# ESP32_with_USBC.net
KiCad netlist of a schematic drawn in Altium Designer
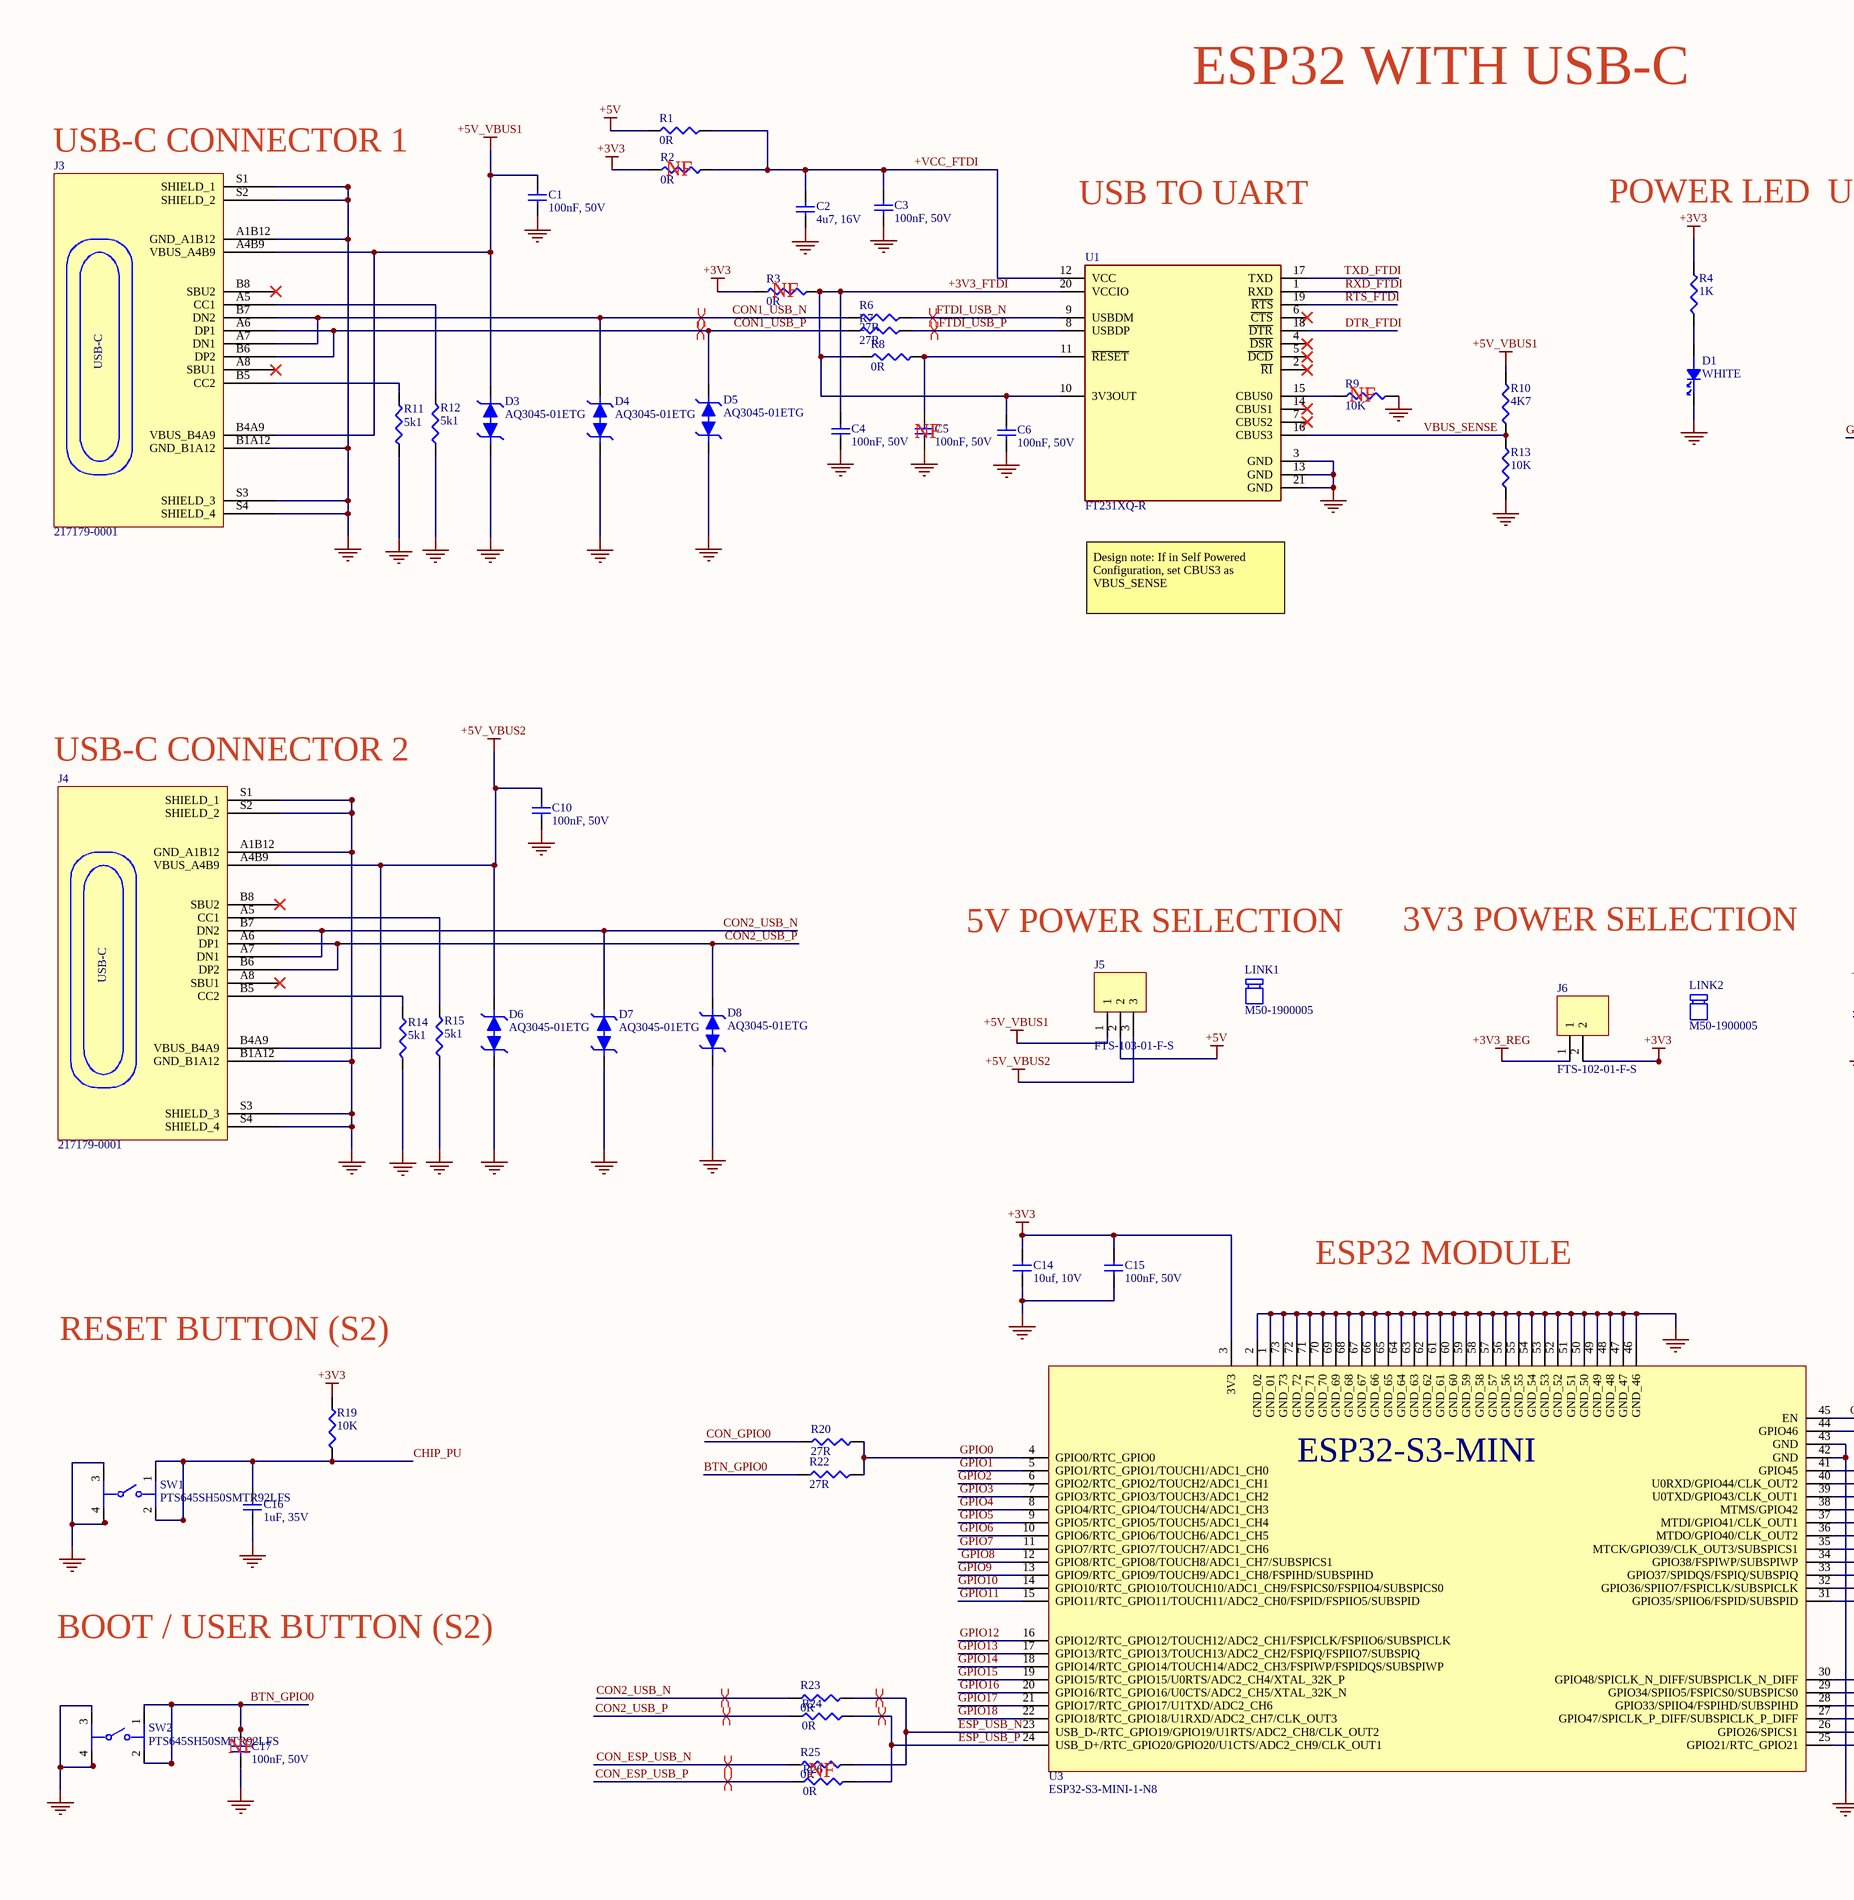
[diagram p0: ESP32 with USBC.SchDoc, left]
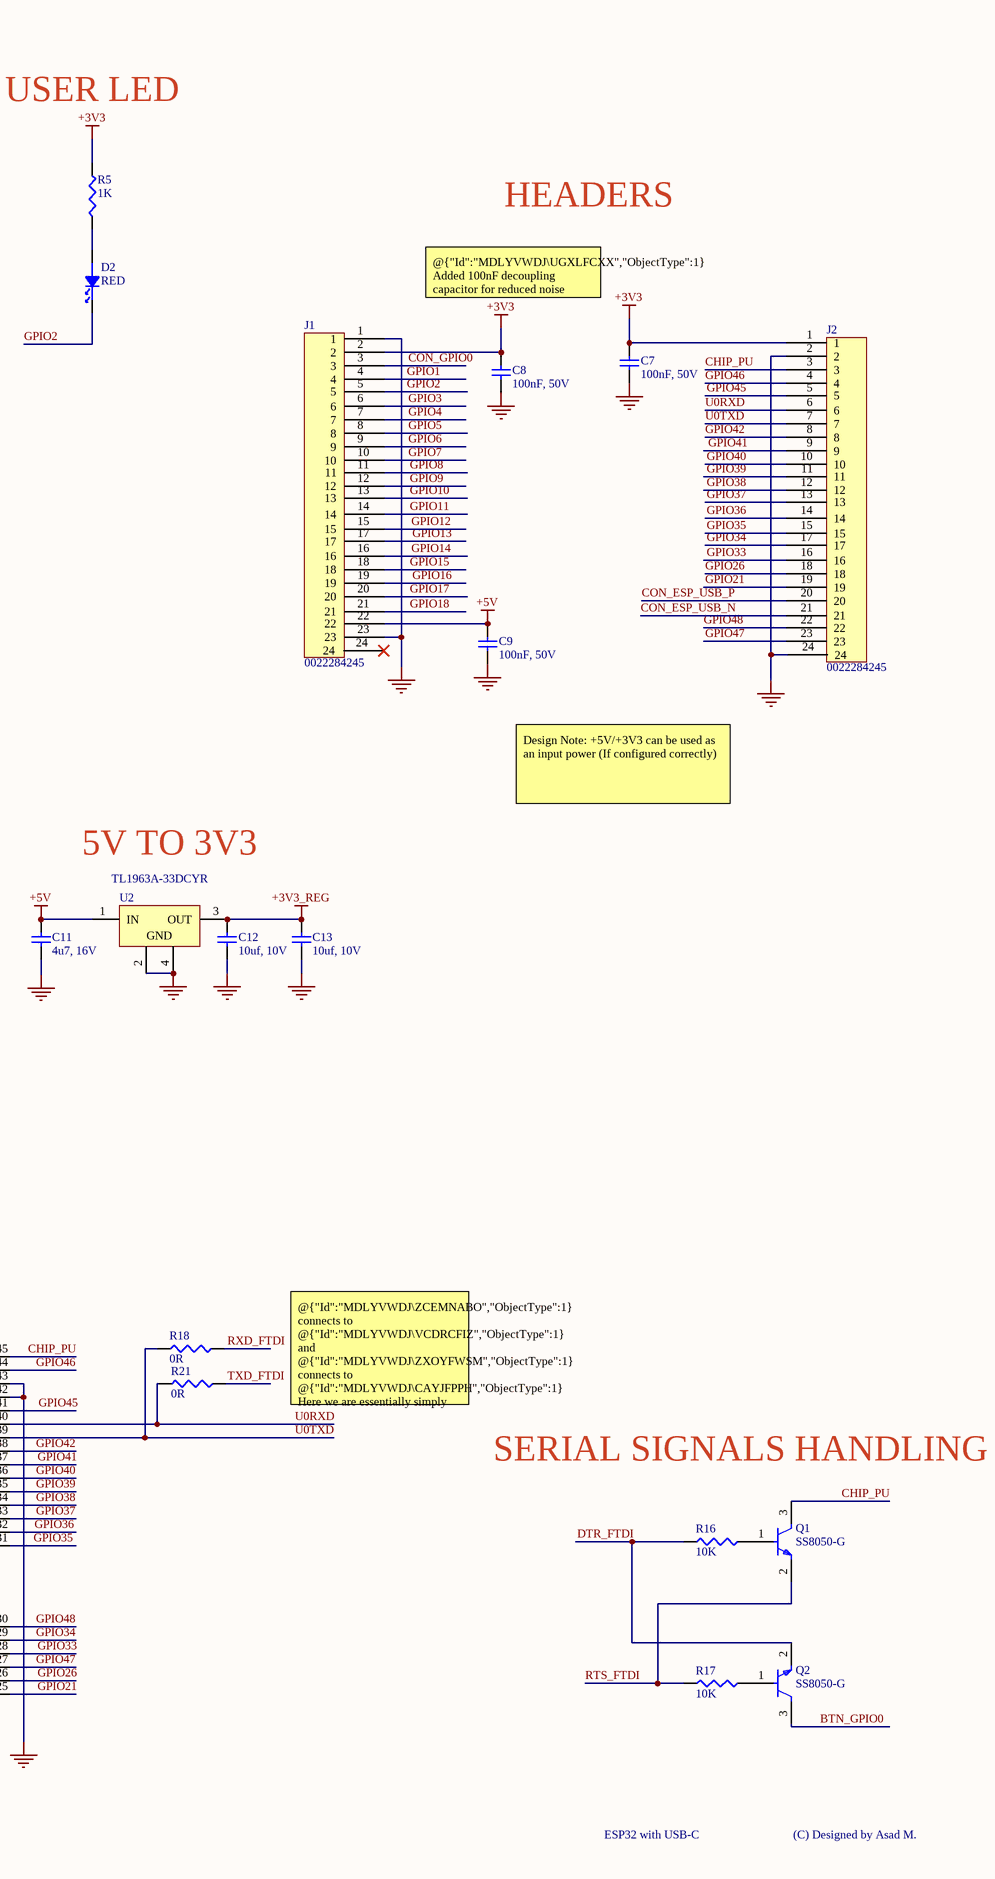
[diagram p1: ESP32 with USBC.SchDoc, right]

(export (version "E")
  (design (tool "Eeschema 10.0.6"))
  (components
    (comp (ref "C1")
      (value "100nF, 50V")
      (footprint "CAPC1005X55N")
      (description "CAP CER 0.1UF 50V X7R 0402")
      (fields
        (field (name "MANUFACTURER") "Samsung")
        (field (name "MANUFACTURER PART NUMBER") "CL05B104KB5NNNC")
      )
      (libsource (lib "Schlib") (part "CL05B104KB5NNNC"))
    )
    (comp (ref "C2")
      (value "4u7, 16V")
      (footprint "CAPC1005X55N")
      (description "CAP CER 4.7UF 16V X5R 0402")
      (fields
        (field (name "MANUFACTURER") "Samsung")
        (field (name "MANUFACTURER PART NUMBER") "CL05A475MO5NUNC")
      )
      (libsource (lib "Schlib") (part "CL05A475MO5NUNC"))
    )
    (comp (ref "C3")
      (value "100nF, 50V")
      (footprint "CAPC1005X55N")
      (description "CAP CER 0.1UF 50V X7R 0402")
      (fields
        (field (name "MANUFACTURER") "Samsung")
        (field (name "MANUFACTURER PART NUMBER") "CL05B104KB5NNNC")
      )
      (libsource (lib "Schlib") (part "CL05B104KB5NNNC"))
    )
    (comp (ref "C4")
      (value "100nF, 50V")
      (footprint "CAPC1005X55N")
      (description "CAP CER 0.1UF 50V X7R 0402")
      (fields
        (field (name "MANUFACTURER") "Samsung")
        (field (name "MANUFACTURER PART NUMBER") "CL05B104KB5NNNC")
      )
      (libsource (lib "Schlib") (part "CL05B104KB5NNNC"))
    )
    (comp (ref "C5")
      (value "100nF, 50V")
      (footprint "CAPC1005X55N")
      (description "CAP CER 0.1UF 50V X7R 0402")
      (fields
        (field (name "MANUFACTURER") "Samsung")
        (field (name "MANUFACTURER PART NUMBER") "CL05B104KB5NNNC")
      )
      (libsource (lib "Schlib") (part "CL05B104KB5NNNC"))
    )
    (comp (ref "C6")
      (value "100nF, 50V")
      (footprint "CAPC1005X55N")
      (description "CAP CER 0.1UF 50V X7R 0402")
      (fields
        (field (name "MANUFACTURER") "Samsung")
        (field (name "MANUFACTURER PART NUMBER") "CL05B104KB5NNNC")
      )
      (libsource (lib "Schlib") (part "CL05B104KB5NNNC"))
    )
    (comp (ref "C7")
      (value "100nF, 50V")
      (footprint "CAPC1005X55N")
      (description "CAP CER 0.1UF 50V X7R 0402")
      (fields
        (field (name "MANUFACTURER") "Samsung")
        (field (name "MANUFACTURER PART NUMBER") "CL05B104KB5NNNC")
      )
      (libsource (lib "Schlib") (part "CL05B104KB5NNNC"))
    )
    (comp (ref "C8")
      (value "100nF, 50V")
      (footprint "CAPC1005X55N")
      (description "CAP CER 0.1UF 50V X7R 0402")
      (fields
        (field (name "MANUFACTURER") "Samsung")
        (field (name "MANUFACTURER PART NUMBER") "CL05B104KB5NNNC")
      )
      (libsource (lib "Schlib") (part "CL05B104KB5NNNC"))
    )
    (comp (ref "C9")
      (value "100nF, 50V")
      (footprint "CAPC1005X55N")
      (description "CAP CER 0.1UF 50V X7R 0402")
      (fields
        (field (name "MANUFACTURER") "Samsung")
        (field (name "MANUFACTURER PART NUMBER") "CL05B104KB5NNNC")
      )
      (libsource (lib "Schlib") (part "CL05B104KB5NNNC"))
    )
    (comp (ref "C10")
      (value "100nF, 50V")
      (footprint "CAPC1005X55N")
      (description "CAP CER 0.1UF 50V X7R 0402")
      (fields
        (field (name "MANUFACTURER") "Samsung")
        (field (name "MANUFACTURER PART NUMBER") "CL05B104KB5NNNC")
      )
      (libsource (lib "Schlib") (part "CL05B104KB5NNNC"))
    )
    (comp (ref "C11")
      (value "4u7, 16V")
      (footprint "CAPC1005X55N")
      (description "CAP CER 4.7UF 16V X5R 0402")
      (fields
        (field (name "MANUFACTURER") "Samsung")
        (field (name "MANUFACTURER PART NUMBER") "CL05A475MO5NUNC")
      )
      (libsource (lib "Schlib") (part "CL05A475MO5NUNC"))
    )
    (comp (ref "C12")
      (value "10uf, 10V")
      (footprint "CAPC1005X55N")
      (description "CAP CER 10UF 10V X5R 0402")
      (fields
        (field (name "MANUFACTURER") "Samsung")
        (field (name "MANUFACTURER PART NUMBER") "CL05A106MP8NUB8")
      )
      (libsource (lib "Schlib") (part "CL05A106MP8NUB8"))
    )
    (comp (ref "C13")
      (value "10uf, 10V")
      (footprint "CAPC1005X55N")
      (description "CAP CER 10UF 10V X5R 0402")
      (fields
        (field (name "MANUFACTURER") "Samsung")
        (field (name "MANUFACTURER PART NUMBER") "CL05A106MP8NUB8")
      )
      (libsource (lib "Schlib") (part "CL05A106MP8NUB8"))
    )
    (comp (ref "C14")
      (value "10uf, 10V")
      (footprint "CAPC1005X55N")
      (description "CAP CER 10UF 10V X5R 0402")
      (fields
        (field (name "MANUFACTURER") "Samsung")
        (field (name "MANUFACTURER PART NUMBER") "CL05A106MP8NUB8")
      )
      (libsource (lib "Schlib") (part "CL05A106MP8NUB8"))
    )
    (comp (ref "C15")
      (value "100nF, 50V")
      (footprint "CAPC1005X55N")
      (description "CAP CER 0.1UF 50V X7R 0402")
      (fields
        (field (name "MANUFACTURER") "Samsung")
        (field (name "MANUFACTURER PART NUMBER") "CL05B104KB5NNNC")
      )
      (libsource (lib "Schlib") (part "CL05B104KB5NNNC"))
    )
    (comp (ref "C16")
      (value "1uF, 35V")
      (footprint "CAPC1005X55N")
      (description "CAP CER 1UF 35V X5R 0402")
      (fields
        (field (name "MANUFACTURER") "Samsung")
        (field (name "MANUFACTURER PART NUMBER") "CL05A105KL5NRNC")
      )
      (libsource (lib "Schlib") (part "CL05A105KL5NRNC"))
    )
    (comp (ref "C17")
      (value "100nF, 50V")
      (footprint "CAPC1005X55N")
      (description "CAP CER 0.1UF 50V X7R 0402")
      (fields
        (field (name "MANUFACTURER") "Samsung")
        (field (name "MANUFACTURER PART NUMBER") "CL05B104KB5NNNC")
      )
      (libsource (lib "Schlib") (part "CL05B104KB5NNNC"))
    )
    (comp (ref "D1")
      (value "WHITE")
      (description "LED COOL WHITE DIFFUSED 0402 SMD")
      (fields
        (field (name "MANUFACTURER") "Vishay")
        (field (name "MANUFACTURER PART NUMBER") "VLMW1500-GS08")
      )
      (libsource (lib "Schlib") (part "VLMW1500-GS08"))
    )
    (comp (ref "D2")
      (value "RED")
      (description "LED RED 0402 SMD")
      (fields
        (field (name "MANUFACTURER") "Vishay")
        (field (name "MANUFACTURER PART NUMBER") "VLMS1500-GS08")
      )
      (libsource (lib "Schlib") (part "VLMS1500-GS08"))
    )
    (comp (ref "D3")
      (value "AQ3045-01ETG")
      (description "TVS DIODE 5.3VWM 12VC SOD882")
      (fields (field (name "MANUFACTURER") "Littelfuse") (field (name "LCSC PART NUMBER") "C3710326"))
      (libsource (lib "Schlib") (part "AQ3045-01ETG"))
    )
    (comp (ref "D4")
      (value "AQ3045-01ETG")
      (description "TVS DIODE 5.3VWM 12VC SOD882")
      (fields (field (name "MANUFACTURER") "Littelfuse") (field (name "LCSC PART NUMBER") "C3710326"))
      (libsource (lib "Schlib") (part "AQ3045-01ETG"))
    )
    (comp (ref "D5")
      (value "AQ3045-01ETG")
      (description "TVS DIODE 5.3VWM 12VC SOD882")
      (fields (field (name "MANUFACTURER") "Littelfuse") (field (name "LCSC PART NUMBER") "C3710326"))
      (libsource (lib "Schlib") (part "AQ3045-01ETG"))
    )
    (comp (ref "D6")
      (value "AQ3045-01ETG")
      (description "TVS DIODE 5.3VWM 12VC SOD882")
      (fields (field (name "MANUFACTURER") "Littelfuse") (field (name "LCSC PART NUMBER") "C3710326"))
      (libsource (lib "Schlib") (part "AQ3045-01ETG"))
    )
    (comp (ref "D7")
      (value "AQ3045-01ETG")
      (description "TVS DIODE 5.3VWM 12VC SOD882")
      (fields (field (name "MANUFACTURER") "Littelfuse") (field (name "LCSC PART NUMBER") "C3710326"))
      (libsource (lib "Schlib") (part "AQ3045-01ETG"))
    )
    (comp (ref "D8")
      (value "AQ3045-01ETG")
      (description "TVS DIODE 5.3VWM 12VC SOD882")
      (fields (field (name "MANUFACTURER") "Littelfuse") (field (name "LCSC PART NUMBER") "C3710326"))
      (libsource (lib "Schlib") (part "AQ3045-01ETG"))
    )
    (comp (ref "J1")
      (value "0022284245")
      (footprint "HDR_1X24_2.54MM")
      (description "CONN HEADER VERT 24POS 2.54MM")
      (fields (field (name "MANUFACTURER") "Molex") (field (name "MANUFACTURER PART NUMBER") "22-28-4245"))
      (libsource (lib "") (part "0022284245_1"))
    )
    (comp (ref "J2")
      (value "0022284245")
      (footprint "HDR_1X24_2.54MM")
      (description "CONN HEADER VERT 24POS 2.54MM")
      (fields (field (name "MANUFACTURER") "Molex") (field (name "MANUFACTURER PART NUMBER") "22-28-4245"))
      (libsource (lib "Schlib") (part "0022284245"))
    )
    (comp (ref "J3")
      (value "217179-0001")
      (footprint "FP-2171790001-MFG")
      (description "CONN RCP USB2.0 TYP C 24P SMD RA")
      (fields (field (name "MANUFACTURER") "Molex") (field (name "LCSC PART NUMBER") "C3197684"))
      (libsource (lib "Schlib") (part "217179-0001"))
    )
    (comp (ref "J4")
      (value "217179-0001")
      (footprint "FP-2171790001-MFG")
      (description "CONN RCP USB2.0 TYP C 24P SMD RA")
      (fields (field (name "MANUFACTURER") "Molex") (field (name "LCSC PART NUMBER") "C3197684"))
      (libsource (lib "Schlib") (part "217179-0001"))
    )
    (comp (ref "J5")
      (value "FTS-103-01-F-S")
      (footprint "HDR_1X3_1.27MM")
      (description "CONN HEADER VERT 3POS 1.27MM")
      (fields (field (name "MANUFACTURER") "Samtec") (field (name "LCSC PART NUMBER") "C3333578"))
      (libsource (lib "Schlib") (part "FTS-103-01-F-S"))
    )
    (comp (ref "J6")
      (value "FTS-102-01-F-S")
      (footprint "HDR_1X2_1.27MM")
      (description "CONN HEADER VERT 2POS 1.27MM")
      (fields (field (name "MANUFACTURER") "Samtec") (field (name "LCSC PART NUMBER") "C6045317"))
      (libsource (lib "Schlib") (part "FTS-102-01-F-S"))
    )
    (comp (ref "LINK1")
      (value "M50-1900005")
      (description "CONN SHUNT 1.27MM BLACK")
      (fields (field (name "MANUFACTURER") "Harwin") (field (name "LCSC PART NUMBER") "C6293276"))
      (libsource (lib "Schlib") (part "M50-1900005"))
    )
    (comp (ref "LINK2")
      (value "M50-1900005")
      (description "CONN SHUNT 1.27MM BLACK")
      (fields (field (name "MANUFACTURER") "Harwin") (field (name "LCSC PART NUMBER") "C6293276"))
      (libsource (lib "Schlib") (part "M50-1900005"))
    )
    (comp (ref "Q1")
      (value "SS8050-G")
      (footprint "FP-SS8050-G-IPC_B")
      (description "TRANS NPN 25V 1.5A SOT-23-3")
      (fields (field (name "MANUFACTURER") "Comchip") (field (name "LCSC PART NUMBER") "C164886"))
      (libsource (lib "Schlib") (part "SS8050-G"))
    )
    (comp (ref "Q2")
      (value "SS8050-G")
      (footprint "FP-SS8050-G-IPC_B")
      (description "TRANS NPN 25V 1.5A SOT-23-3")
      (fields (field (name "MANUFACTURER") "Comchip") (field (name "LCSC PART NUMBER") "C164886"))
      (libsource (lib "Schlib") (part "SS8050-G"))
    )
    (comp (ref "R1")
      (value "0R")
      (footprint "RESC1005X37N")
      (description "RES 0 OHM JUMPER 1/16W 0402")
      (fields
        (field (name "MANUFACTURER") "Yageo")
        (field (name "MANUFACTURER PART NUMBER") "RC0402JR-070RL")
      )
      (libsource (lib "Schlib") (part "RC0402JR-070RL"))
    )
    (comp (ref "R2")
      (value "0R")
      (footprint "RESC1005X37N")
      (description "RES 0 OHM JUMPER 1/16W 0402")
      (fields
        (field (name "MANUFACTURER") "Yageo")
        (field (name "MANUFACTURER PART NUMBER") "RC0402JR-070RL")
      )
      (libsource (lib "Schlib") (part "RC0402JR-070RL"))
    )
    (comp (ref "R3")
      (value "0R")
      (footprint "RESC1005X37N")
      (description "RES 0 OHM JUMPER 1/16W 0402")
      (fields
        (field (name "MANUFACTURER") "Yageo")
        (field (name "MANUFACTURER PART NUMBER") "RC0402JR-070RL")
      )
      (libsource (lib "Schlib") (part "RC0402JR-070RL"))
    )
    (comp (ref "R4")
      (value "1K")
      (footprint "RESC1005X37N")
      (description "RES 1K OHM 1% 1/16W 0402")
      (fields
        (field (name "MANUFACTURER") "Yageo")
        (field (name "MANUFACTURER PART NUMBER") "RC0402FR-071KL")
      )
      (libsource (lib "Schlib") (part "RC0402FR-071KL"))
    )
    (comp (ref "R5")
      (value "1K")
      (footprint "RESC1005X37N")
      (description "RES 1K OHM 1% 1/16W 0402")
      (fields
        (field (name "MANUFACTURER") "Yageo")
        (field (name "MANUFACTURER PART NUMBER") "RC0402FR-071KL")
      )
      (libsource (lib "Schlib") (part "RC0402FR-071KL"))
    )
    (comp (ref "R6")
      (value "27R")
      (footprint "RESC1005X37N")
      (description "RES 27 OHM 1% 1/16W 0402")
      (fields
        (field (name "MANUFACTURER") "Yageo")
        (field (name "MANUFACTURER PART NUMBER") "RC0402FR-0727RL")
      )
      (libsource (lib "Schlib") (part "RC0402FR-0727RL"))
    )
    (comp (ref "R7")
      (value "27R")
      (footprint "RESC1005X37N")
      (description "RES 27 OHM 1% 1/16W 0402")
      (fields
        (field (name "MANUFACTURER") "Yageo")
        (field (name "MANUFACTURER PART NUMBER") "RC0402FR-0727RL")
      )
      (libsource (lib "Schlib") (part "RC0402FR-0727RL"))
    )
    (comp (ref "R8")
      (value "0R")
      (footprint "RESC1005X37N")
      (description "RES 0 OHM JUMPER 1/16W 0402")
      (fields
        (field (name "MANUFACTURER") "Yageo")
        (field (name "MANUFACTURER PART NUMBER") "RC0402JR-070RL")
      )
      (libsource (lib "Schlib") (part "RC0402JR-070RL"))
    )
    (comp (ref "R9")
      (value "10K")
      (footprint "RESC1005X37N")
      (description "RES SMD 10K OHM 1% 1/16W 0402")
      (fields
        (field (name "MANUFACTURER") "Yageo")
        (field (name "MANUFACTURER PART NUMBER") "AC0402FR-0710KL")
      )
      (libsource (lib "Schlib") (part "AC0402FR-0710KL"))
    )
    (comp (ref "R10")
      (value "4K7")
      (footprint "RESC1005X37N")
      (description "RES 4.7K OHM 1% 1/16W 0402")
      (fields
        (field (name "MANUFACTURER") "Yageo")
        (field (name "MANUFACTURER PART NUMBER") "RC0402FR-074K7L")
      )
      (libsource (lib "Schlib") (part "RC0402FR-074K7L"))
    )
    (comp (ref "R11")
      (value "5k1")
      (footprint "RESC1005X37N")
      (description "RES SMD 5.1K OHM 1% 1/16W 0402")
      (fields
        (field (name "MANUFACTURER") "Yageo")
        (field (name "MANUFACTURER PART NUMBER") "AC0402FR-075K1L")
      )
      (libsource (lib "Schlib") (part "AC0402FR-075K1L"))
    )
    (comp (ref "R12")
      (value "5k1")
      (footprint "RESC1005X37N")
      (description "RES SMD 5.1K OHM 1% 1/16W 0402")
      (fields
        (field (name "MANUFACTURER") "Yageo")
        (field (name "MANUFACTURER PART NUMBER") "AC0402FR-075K1L")
      )
      (libsource (lib "Schlib") (part "AC0402FR-075K1L"))
    )
    (comp (ref "R13")
      (value "10K")
      (footprint "RESC1005X37N")
      (description "RES SMD 10K OHM 1% 1/16W 0402")
      (fields
        (field (name "MANUFACTURER") "Yageo")
        (field (name "MANUFACTURER PART NUMBER") "AC0402FR-0710KL")
      )
      (libsource (lib "Schlib") (part "AC0402FR-0710KL"))
    )
    (comp (ref "R14")
      (value "5k1")
      (footprint "RESC1005X37N")
      (description "RES SMD 5.1K OHM 1% 1/16W 0402")
      (fields
        (field (name "MANUFACTURER") "Yageo")
        (field (name "MANUFACTURER PART NUMBER") "AC0402FR-075K1L")
      )
      (libsource (lib "Schlib") (part "AC0402FR-075K1L"))
    )
    (comp (ref "R15")
      (value "5k1")
      (footprint "RESC1005X37N")
      (description "RES SMD 5.1K OHM 1% 1/16W 0402")
      (fields
        (field (name "MANUFACTURER") "Yageo")
        (field (name "MANUFACTURER PART NUMBER") "AC0402FR-075K1L")
      )
      (libsource (lib "Schlib") (part "AC0402FR-075K1L"))
    )
    (comp (ref "R16")
      (value "10K")
      (footprint "RESC1005X37N")
      (description "RES SMD 10K OHM 1% 1/16W 0402")
      (fields
        (field (name "MANUFACTURER") "Yageo")
        (field (name "MANUFACTURER PART NUMBER") "AC0402FR-0710KL")
      )
      (libsource (lib "Schlib") (part "AC0402FR-0710KL"))
    )
    (comp (ref "R17")
      (value "10K")
      (footprint "RESC1005X37N")
      (description "RES SMD 10K OHM 1% 1/16W 0402")
      (fields
        (field (name "MANUFACTURER") "Yageo")
        (field (name "MANUFACTURER PART NUMBER") "AC0402FR-0710KL")
      )
      (libsource (lib "Schlib") (part "AC0402FR-0710KL"))
    )
    (comp (ref "R18")
      (value "0R")
      (footprint "RESC1005X37N")
      (description "RES 0 OHM JUMPER 1/16W 0402")
      (fields
        (field (name "MANUFACTURER") "Yageo")
        (field (name "MANUFACTURER PART NUMBER") "RC0402JR-070RL")
      )
      (libsource (lib "Schlib") (part "RC0402JR-070RL"))
    )
    (comp (ref "R19")
      (value "10K")
      (footprint "RESC1005X37N")
      (description "RES SMD 10K OHM 1% 1/16W 0402")
      (fields
        (field (name "MANUFACTURER") "Yageo")
        (field (name "MANUFACTURER PART NUMBER") "AC0402FR-0710KL")
      )
      (libsource (lib "Schlib") (part "AC0402FR-0710KL"))
    )
    (comp (ref "R20")
      (value "27R")
      (footprint "RESC1005X37N")
      (description "RES 27 OHM 1% 1/16W 0402")
      (fields
        (field (name "MANUFACTURER") "Yageo")
        (field (name "MANUFACTURER PART NUMBER") "RC0402FR-0727RL")
      )
      (libsource (lib "Schlib") (part "RC0402FR-0727RL"))
    )
    (comp (ref "R21")
      (value "0R")
      (footprint "RESC1005X37N")
      (description "RES 0 OHM JUMPER 1/16W 0402")
      (fields
        (field (name "MANUFACTURER") "Yageo")
        (field (name "MANUFACTURER PART NUMBER") "RC0402JR-070RL")
      )
      (libsource (lib "Schlib") (part "RC0402JR-070RL"))
    )
    (comp (ref "R22")
      (value "27R")
      (footprint "RESC1005X37N")
      (description "RES 27 OHM 1% 1/16W 0402")
      (fields
        (field (name "MANUFACTURER") "Yageo")
        (field (name "MANUFACTURER PART NUMBER") "RC0402FR-0727RL")
      )
      (libsource (lib "Schlib") (part "RC0402FR-0727RL"))
    )
    (comp (ref "R23")
      (value "0R")
      (footprint "RESC1005X37N")
      (description "RES 0 OHM JUMPER 1/16W 0402")
      (fields
        (field (name "MANUFACTURER") "Yageo")
        (field (name "MANUFACTURER PART NUMBER") "RC0402JR-070RL")
      )
      (libsource (lib "Schlib") (part "RC0402JR-070RL"))
    )
    (comp (ref "R24")
      (value "0R")
      (footprint "RESC1005X37N")
      (description "RES 0 OHM JUMPER 1/16W 0402")
      (fields
        (field (name "MANUFACTURER") "Yageo")
        (field (name "MANUFACTURER PART NUMBER") "RC0402JR-070RL")
      )
      (libsource (lib "Schlib") (part "RC0402JR-070RL"))
    )
    (comp (ref "R25")
      (value "0R")
      (footprint "RESC1005X37N")
      (description "RES 0 OHM JUMPER 1/16W 0402")
      (fields
        (field (name "MANUFACTURER") "Yageo")
        (field (name "MANUFACTURER PART NUMBER") "RC0402JR-070RL")
      )
      (libsource (lib "Schlib") (part "RC0402JR-070RL"))
    )
    (comp (ref "R26")
      (value "0R")
      (footprint "RESC1005X37N")
      (description "RES 0 OHM JUMPER 1/16W 0402")
      (fields
        (field (name "MANUFACTURER") "Yageo")
        (field (name "MANUFACTURER PART NUMBER") "RC0402JR-070RL")
      )
      (libsource (lib "Schlib") (part "RC0402JR-070RL"))
    )
    (comp (ref "SW1")
      (value "PTS645SH50SMTR92LFS")
      (footprint "FP-PTS645SH50SMTR92LFS-MFG")
      (description "SWITCH TACTILE SPST-NO 0.05A 12V")
      (fields (field (name "MANUFACTURER") "ITT C&K") (field (name "LCSC PART NUMBER") "C221869"))
      (libsource (lib "Schlib") (part "PTS645SH50SMTR92LFS"))
    )
    (comp (ref "SW2")
      (value "PTS645SH50SMTR92LFS")
      (footprint "FP-PTS645SH50SMTR92LFS-MFG")
      (description "SWITCH TACTILE SPST-NO 0.05A 12V")
      (fields (field (name "MANUFACTURER") "ITT C&K") (field (name "LCSC PART NUMBER") "C221869"))
      (libsource (lib "Schlib") (part "PTS645SH50SMTR92LFS"))
    )
    (comp (ref "U1")
      (value "FT231XQ-R")
      (footprint "FP-QFN-20-IPC_B")
      (description "IC USB SERIAL FULL UART 20QFN")
      (fields (field (name "MANUFACTURER") "FTDI") (field (name "LCSC PART NUMBER") "C132159"))
      (libsource (lib "Schlib") (part "FT231XQ-R"))
    )
    (comp (ref "U2")
      (value "TL1963A-33DCYR")
      (description "IC REG LINEAR 3.3V 1.5A SOT223-4")
      (fields (field (name "MANUFACTURER") "Texas Instruments") (field (name "LCSC PART NUMBER") "C181262"))
      (libsource (lib "Schlib") (part "TL1963A-33DCYR"))
    )
    (comp (ref "U3")
      (value "ESP32-S3-MINI-1-N8")
      (description "SMD module, ESP32-S3FN8, 8 MB SPI flash, PCB antenna")
      (fields (field (name "MANUFACTURER") "Espressif Systems") (field (name "LCSC PART NUMBER") "C2913206"))
      (libsource (lib "Schlib") (part "ESP32-S3-MINI-1-N8"))
    )
  )
  (nets
    (net (code "1") (name "+3V3") (class "Default")
      (node (ref "C14") (pin "2") (pinfunction "2_2") (pintype "passive"))
      (node (ref "C15") (pin "2") (pinfunction "2_2") (pintype "passive"))
      (node (ref "C7") (pin "2") (pinfunction "2_2") (pintype "passive"))
      (node (ref "C8") (pin "2") (pinfunction "2_2") (pintype "passive"))
      (node (ref "J1") (pin "2") (pinfunction "2_2") (pintype "passive"))
      (node (ref "J2") (pin "1") (pinfunction "1_1") (pintype "passive"))
      (node (ref "J6") (pin "2") (pinfunction "2_2") (pintype "passive"))
      (node (ref "R19") (pin "2") (pinfunction "2_2") (pintype "passive"))
      (node (ref "R2") (pin "1") (pinfunction "1_1") (pintype "passive"))
      (node (ref "R3") (pin "1") (pinfunction "1_1") (pintype "passive"))
      (node (ref "R4") (pin "2") (pinfunction "2_2") (pintype "passive"))
      (node (ref "R5") (pin "2") (pinfunction "2_2") (pintype "passive"))
      (node (ref "U3") (pin "3") (pinfunction "3V3_3") (pintype "passive"))
    )
    (net (code "2") (name "+3V3_REG") (class "Default")
      (node (ref "C12") (pin "2") (pinfunction "2_2") (pintype "passive"))
      (node (ref "C13") (pin "2") (pinfunction "2_2") (pintype "passive"))
      (node (ref "J6") (pin "1") (pinfunction "1_1") (pintype "passive"))
      (node (ref "U2") (pin "3") (pinfunction "OUT_3") (pintype "power_in"))
    )
    (net (code "3") (name "+5V") (class "Default")
      (node (ref "C11") (pin "2") (pinfunction "2_2") (pintype "passive"))
      (node (ref "C9") (pin "2") (pinfunction "2_2") (pintype "passive"))
      (node (ref "J1") (pin "22") (pinfunction "22_22") (pintype "passive"))
      (node (ref "J5") (pin "2") (pinfunction "2_2") (pintype "passive"))
      (node (ref "R1") (pin "1") (pinfunction "1_1") (pintype "passive"))
      (node (ref "U2") (pin "1") (pinfunction "IN_1") (pintype "power_in"))
    )
    (net (code "4") (name "+5V_VBUS1") (class "Default")
      (node (ref "C1") (pin "2") (pinfunction "2_2") (pintype "passive"))
      (node (ref "D3") (pin "2") (pinfunction "2_2") (pintype "passive"))
      (node (ref "J3") (pin "A4B9") (pinfunction "VBUS_A4B9_A4B9") (pintype "passive"))
      (node (ref "J3") (pin "B4A9") (pinfunction "VBUS_B4A9_B4A9") (pintype "passive"))
      (node (ref "J5") (pin "1") (pinfunction "1_1") (pintype "passive"))
      (node (ref "R10") (pin "2") (pinfunction "2_2") (pintype "passive"))
    )
    (net (code "5") (name "+5V_VBUS2") (class "Default")
      (node (ref "C10") (pin "2") (pinfunction "2_2") (pintype "passive"))
      (node (ref "D6") (pin "2") (pinfunction "2_2") (pintype "passive"))
      (node (ref "J4") (pin "A4B9") (pinfunction "VBUS_A4B9_A4B9") (pintype "passive"))
      (node (ref "J4") (pin "B4A9") (pinfunction "VBUS_B4A9_B4A9") (pintype "passive"))
      (node (ref "J5") (pin "3") (pinfunction "3_3") (pintype "passive"))
    )
    (net (code "6") (name "/+3V3_FTDI") (class "Default")
      (node (ref "C4") (pin "2") (pinfunction "2_2") (pintype "passive"))
      (node (ref "C6") (pin "2") (pinfunction "2_2") (pintype "passive"))
      (node (ref "R3") (pin "2") (pinfunction "2_2") (pintype "passive"))
      (node (ref "R8") (pin "1") (pinfunction "1_1") (pintype "passive"))
      (node (ref "U1") (pin "10") (pinfunction "3V3OUT_10") (pintype "passive"))
      (node (ref "U1") (pin "20") (pinfunction "VCCIO_20") (pintype "passive"))
    )
    (net (code "7") (name "/+VCC_FTDI") (class "Default")
      (node (ref "C2") (pin "2") (pinfunction "2_2") (pintype "passive"))
      (node (ref "C3") (pin "2") (pinfunction "2_2") (pintype "passive"))
      (node (ref "R1") (pin "2") (pinfunction "2_2") (pintype "passive"))
      (node (ref "R2") (pin "2") (pinfunction "2_2") (pintype "passive"))
      (node (ref "U1") (pin "12") (pinfunction "VCC_12") (pintype "passive"))
    )
    (net (code "8") (name "/BTN_GPIO0") (class "Default")
      (node (ref "C17") (pin "2") (pinfunction "2_2") (pintype "passive"))
      (node (ref "Q2") (pin "3") (pinfunction "C_3") (pintype "passive"))
      (node (ref "R22") (pin "1") (pinfunction "1_1") (pintype "passive"))
      (node (ref "SW2") (pin "1") (pinfunction "1_1") (pintype "passive"))
      (node (ref "SW2") (pin "2") (pinfunction "2_2") (pintype "passive"))
    )
    (net (code "9") (name "/CHIP_PU") (class "Default")
      (node (ref "C16") (pin "2") (pinfunction "2_2") (pintype "passive"))
      (node (ref "J2") (pin "3") (pinfunction "3_3") (pintype "passive"))
      (node (ref "Q1") (pin "3") (pinfunction "C_3") (pintype "passive"))
      (node (ref "R19") (pin "1") (pinfunction "1_1") (pintype "passive"))
      (node (ref "SW1") (pin "1") (pinfunction "1_1") (pintype "passive"))
      (node (ref "SW1") (pin "2") (pinfunction "2_2") (pintype "passive"))
      (node (ref "U3") (pin "45") (pinfunction "EN_45") (pintype "passive"))
    )
    (net (code "10") (name "/CON1_USB_N") (class "Default")
      (node (ref "D4") (pin "2") (pinfunction "2_2") (pintype "passive"))
      (node (ref "J3") (pin "A7") (pinfunction "DN1_A7") (pintype "passive"))
      (node (ref "J3") (pin "B7") (pinfunction "DN2_B7") (pintype "passive"))
      (node (ref "R6") (pin "1") (pinfunction "1_1") (pintype "passive"))
    )
    (net (code "11") (name "/CON1_USB_P") (class "Default")
      (node (ref "D5") (pin "2") (pinfunction "2_2") (pintype "passive"))
      (node (ref "J3") (pin "A6") (pinfunction "DP1_A6") (pintype "passive"))
      (node (ref "J3") (pin "B6") (pinfunction "DP2_B6") (pintype "passive"))
      (node (ref "R7") (pin "1") (pinfunction "1_1") (pintype "passive"))
    )
    (net (code "12") (name "/CON2_USB_N") (class "Default")
      (node (ref "D7") (pin "2") (pinfunction "2_2") (pintype "passive"))
      (node (ref "J4") (pin "A7") (pinfunction "DN1_A7") (pintype "passive"))
      (node (ref "J4") (pin "B7") (pinfunction "DN2_B7") (pintype "passive"))
      (node (ref "R23") (pin "1") (pinfunction "1_1") (pintype "passive"))
    )
    (net (code "13") (name "/CON2_USB_P") (class "Default")
      (node (ref "D8") (pin "2") (pinfunction "2_2") (pintype "passive"))
      (node (ref "J4") (pin "A6") (pinfunction "DP1_A6") (pintype "passive"))
      (node (ref "J4") (pin "B6") (pinfunction "DP2_B6") (pintype "passive"))
      (node (ref "R24") (pin "1") (pinfunction "1_1") (pintype "passive"))
    )
    (net (code "14") (name "/CON_ESP_USB_N") (class "Default")
      (node (ref "J2") (pin "21") (pinfunction "21_21") (pintype "passive"))
      (node (ref "R25") (pin "1") (pinfunction "1_1") (pintype "passive"))
    )
    (net (code "15") (name "/CON_ESP_USB_P") (class "Default")
      (node (ref "J2") (pin "20") (pinfunction "20_20") (pintype "passive"))
      (node (ref "R26") (pin "1") (pinfunction "1_1") (pintype "passive"))
    )
    (net (code "16") (name "/CON_GPIO0") (class "Default")
      (node (ref "J1") (pin "3") (pinfunction "3_3") (pintype "passive"))
      (node (ref "R20") (pin "1") (pinfunction "1_1") (pintype "passive"))
    )
    (net (code "17") (name "/DTR_FTDI") (class "Default")
      (node (ref "Q2") (pin "2") (pinfunction "E_2") (pintype "passive"))
      (node (ref "R16") (pin "1") (pinfunction "1_1") (pintype "passive"))
      (node (ref "U1") (pin "18") (pinfunction "~{DTR}_18") (pintype "passive"))
    )
    (net (code "18") (name "/ESP_USB_N") (class "Default")
      (node (ref "R23") (pin "2") (pinfunction "2_2") (pintype "passive"))
      (node (ref "R25") (pin "2") (pinfunction "2_2") (pintype "passive"))
      (node (ref "U3") (pin "23") (pinfunction "USB_D-/RTC_GPIO19/GPIO19/U1RTS/ADC2_CH8/CLK_OUT2_23") (pintype "passive"))
    )
    (net (code "19") (name "/ESP_USB_P") (class "Default")
      (node (ref "R24") (pin "2") (pinfunction "2_2") (pintype "passive"))
      (node (ref "R26") (pin "2") (pinfunction "2_2") (pintype "passive"))
      (node (ref "U3") (pin "24") (pinfunction "USB_D+/RTC_GPIO20/GPIO20/U1CTS/ADC2_CH9/CLK_OUT1_24") (pintype "passive"))
    )
    (net (code "20") (name "/FTDI_USB_N") (class "Default")
      (node (ref "R6") (pin "2") (pinfunction "2_2") (pintype "passive"))
      (node (ref "U1") (pin "9") (pinfunction "USBDM_9") (pintype "passive"))
    )
    (net (code "21") (name "/FTDI_USB_P") (class "Default")
      (node (ref "R7") (pin "2") (pinfunction "2_2") (pintype "passive"))
      (node (ref "U1") (pin "8") (pinfunction "USBDP_8") (pintype "passive"))
    )
    (net (code "22") (name "/GPIO0") (class "Default")
      (node (ref "R20") (pin "2") (pinfunction "2_2") (pintype "passive"))
      (node (ref "R22") (pin "2") (pinfunction "2_2") (pintype "passive"))
      (node (ref "U3") (pin "4") (pinfunction "GPIO0/RTC_GPIO0_4") (pintype "passive"))
    )
    (net (code "23") (name "/GPIO1") (class "Default")
      (node (ref "J1") (pin "4") (pinfunction "4_4") (pintype "passive"))
      (node (ref "U3") (pin "5") (pinfunction "GPIO1/RTC_GPIO1/TOUCH1/ADC1_CH0_5") (pintype "passive"))
    )
    (net (code "24") (name "/GPIO2") (class "Default")
      (node (ref "D2") (pin "1") (pinfunction "1_1") (pintype "passive"))
      (node (ref "J1") (pin "5") (pinfunction "5_5") (pintype "passive"))
      (node (ref "U3") (pin "6") (pinfunction "GPIO2/RTC_GPIO2/TOUCH2/ADC1_CH1_6") (pintype "passive"))
    )
    (net (code "25") (name "/GPIO3") (class "Default")
      (node (ref "J1") (pin "6") (pinfunction "6_6") (pintype "passive"))
      (node (ref "U3") (pin "7") (pinfunction "GPIO3/RTC_GPIO3/TOUCH3/ADC1_CH2_7") (pintype "passive"))
    )
    (net (code "26") (name "/GPIO4") (class "Default")
      (node (ref "J1") (pin "7") (pinfunction "7_7") (pintype "passive"))
      (node (ref "U3") (pin "8") (pinfunction "GPIO4/RTC_GPIO4/TOUCH4/ADC1_CH3_8") (pintype "passive"))
    )
    (net (code "27") (name "/GPIO5") (class "Default")
      (node (ref "J1") (pin "8") (pinfunction "8_8") (pintype "passive"))
      (node (ref "U3") (pin "9") (pinfunction "GPIO5/RTC_GPIO5/TOUCH5/ADC1_CH4_9") (pintype "passive"))
    )
    (net (code "28") (name "/GPIO6") (class "Default")
      (node (ref "J1") (pin "9") (pinfunction "9_9") (pintype "passive"))
      (node (ref "U3") (pin "10") (pinfunction "GPIO6/RTC_GPIO6/TOUCH6/ADC1_CH5_10") (pintype "passive"))
    )
    (net (code "29") (name "/GPIO7") (class "Default")
      (node (ref "J1") (pin "10") (pinfunction "10_10") (pintype "passive"))
      (node (ref "U3") (pin "11") (pinfunction "GPIO7/RTC_GPIO7/TOUCH7/ADC1_CH6_11") (pintype "passive"))
    )
    (net (code "30") (name "/GPIO8") (class "Default")
      (node (ref "J1") (pin "11") (pinfunction "11_11") (pintype "passive"))
      (node (ref "U3") (pin "12") (pinfunction "GPIO8/RTC_GPIO8/TOUCH8/ADC1_CH7/SUBSPICS1_12") (pintype "passive"))
    )
    (net (code "31") (name "/GPIO9") (class "Default")
      (node (ref "J1") (pin "12") (pinfunction "12_12") (pintype "passive"))
      (node (ref "U3") (pin "13") (pinfunction "GPIO9/RTC_GPIO9/TOUCH9/ADC1_CH8/FSPIHD/SUBSPIHD_13") (pintype "passive"))
    )
    (net (code "32") (name "/GPIO10") (class "Default")
      (node (ref "J1") (pin "13") (pinfunction "13_13") (pintype "passive"))
      (node (ref "U3") (pin "14") (pinfunction "GPIO10/RTC_GPIO10/TOUCH10/ADC1_CH9/FSPICS0/FSPIIO4/SUBSPICS0_14") (pintype "passive"))
    )
    (net (code "33") (name "/GPIO11") (class "Default")
      (node (ref "J1") (pin "14") (pinfunction "14_14") (pintype "passive"))
      (node (ref "U3") (pin "15") (pinfunction "GPIO11/RTC_GPIO11/TOUCH11/ADC2_CH0/FSPID/FSPIIO5/SUBSPID_15") (pintype "passive"))
    )
    (net (code "34") (name "/GPIO12") (class "Default")
      (node (ref "J1") (pin "15") (pinfunction "15_15") (pintype "passive"))
      (node (ref "U3") (pin "16") (pinfunction "GPIO12/RTC_GPIO12/TOUCH12/ADC2_CH1/FSPICLK/FSPIIO6/SUBSPICLK_16") (pintype "passive"))
    )
    (net (code "35") (name "/GPIO13") (class "Default")
      (node (ref "J1") (pin "17") (pinfunction "17_17") (pintype "passive"))
      (node (ref "U3") (pin "17") (pinfunction "GPIO13/RTC_GPIO13/TOUCH13/ADC2_CH2/FSPIQ/FSPIIO7/SUBSPIQ_17") (pintype "passive"))
    )
    (net (code "36") (name "/GPIO14") (class "Default")
      (node (ref "J1") (pin "16") (pinfunction "16_16") (pintype "passive"))
      (node (ref "U3") (pin "18") (pinfunction "GPIO14/RTC_GPIO14/TOUCH14/ADC2_CH3/FSPIWP/FSPIDQS/SUBSPIWP_18") (pintype "passive"))
    )
    (net (code "37") (name "/GPIO15") (class "Default")
      (node (ref "J1") (pin "18") (pinfunction "18_18") (pintype "passive"))
      (node (ref "U3") (pin "19") (pinfunction "GPIO15/RTC_GPIO15/U0RTS/ADC2_CH4/XTAL_32K_P_19") (pintype "passive"))
    )
    (net (code "38") (name "/GPIO16") (class "Default")
      (node (ref "J1") (pin "19") (pinfunction "19_19") (pintype "passive"))
      (node (ref "U3") (pin "20") (pinfunction "GPIO16/RTC_GPIO16/U0CTS/ADC2_CH5/XTAL_32K_N_20") (pintype "passive"))
    )
    (net (code "39") (name "/GPIO17") (class "Default")
      (node (ref "J1") (pin "20") (pinfunction "20_20") (pintype "passive"))
      (node (ref "U3") (pin "21") (pinfunction "GPIO17/RTC_GPIO17/U1TXD/ADC2_CH6_21") (pintype "passive"))
    )
    (net (code "40") (name "/GPIO18") (class "Default")
      (node (ref "J1") (pin "21") (pinfunction "21_21") (pintype "passive"))
      (node (ref "U3") (pin "22") (pinfunction "GPIO18/RTC_GPIO18/U1RXD/ADC2_CH7/CLK_OUT3_22") (pintype "passive"))
    )
    (net (code "41") (name "/GPIO21") (class "Default")
      (node (ref "J2") (pin "19") (pinfunction "19_19") (pintype "passive"))
      (node (ref "U3") (pin "25") (pinfunction "GPIO21/RTC_GPIO21_25") (pintype "passive"))
    )
    (net (code "42") (name "/GPIO26") (class "Default")
      (node (ref "J2") (pin "18") (pinfunction "18_18") (pintype "passive"))
      (node (ref "U3") (pin "26") (pinfunction "GPIO26/SPICS1_26") (pintype "passive"))
    )
    (net (code "43") (name "/GPIO33") (class "Default")
      (node (ref "J2") (pin "16") (pinfunction "16_16") (pintype "passive"))
      (node (ref "U3") (pin "28") (pinfunction "GPIO33/SPIIO4/FSPIHD/SUBSPIHD_28") (pintype "passive"))
    )
    (net (code "44") (name "/GPIO34") (class "Default")
      (node (ref "J2") (pin "17") (pinfunction "17_17") (pintype "passive"))
      (node (ref "U3") (pin "29") (pinfunction "GPIO34/SPIIO5/FSPICS0/SUBSPICS0_29") (pintype "passive"))
    )
    (net (code "45") (name "/GPIO35") (class "Default")
      (node (ref "J2") (pin "15") (pinfunction "15_15") (pintype "passive"))
      (node (ref "U3") (pin "31") (pinfunction "GPIO35/SPIIO6/FSPID/SUBSPID_31") (pintype "passive"))
    )
    (net (code "46") (name "/GPIO36") (class "Default")
      (node (ref "J2") (pin "14") (pinfunction "14_14") (pintype "passive"))
      (node (ref "U3") (pin "32") (pinfunction "GPIO36/SPIIO7/FSPICLK/SUBSPICLK_32") (pintype "passive"))
    )
    (net (code "47") (name "/GPIO37") (class "Default")
      (node (ref "J2") (pin "13") (pinfunction "13_13") (pintype "passive"))
      (node (ref "U3") (pin "33") (pinfunction "GPIO37/SPIDQS/FSPIQ/SUBSPIQ_33") (pintype "passive"))
    )
    (net (code "48") (name "/GPIO38") (class "Default")
      (node (ref "J2") (pin "12") (pinfunction "12_12") (pintype "passive"))
      (node (ref "U3") (pin "34") (pinfunction "GPIO38/FSPIWP/SUBSPIWP_34") (pintype "passive"))
    )
    (net (code "49") (name "/GPIO39") (class "Default")
      (node (ref "J2") (pin "11") (pinfunction "11_11") (pintype "passive"))
      (node (ref "U3") (pin "35") (pinfunction "MTCK/GPIO39/CLK_OUT3/SUBSPICS1_35") (pintype "passive"))
    )
    (net (code "50") (name "/GPIO40") (class "Default")
      (node (ref "J2") (pin "10") (pinfunction "10_10") (pintype "passive"))
      (node (ref "U3") (pin "36") (pinfunction "MTDO/GPIO40/CLK_OUT2_36") (pintype "passive"))
    )
    (net (code "51") (name "/GPIO41") (class "Default")
      (node (ref "J2") (pin "9") (pinfunction "9_9") (pintype "passive"))
      (node (ref "U3") (pin "37") (pinfunction "MTDI/GPIO41/CLK_OUT1_37") (pintype "passive"))
    )
    (net (code "52") (name "/GPIO42") (class "Default")
      (node (ref "J2") (pin "8") (pinfunction "8_8") (pintype "passive"))
      (node (ref "U3") (pin "38") (pinfunction "MTMS/GPIO42_38") (pintype "passive"))
    )
    (net (code "53") (name "/GPIO45") (class "Default")
      (node (ref "J2") (pin "5") (pinfunction "5_5") (pintype "passive"))
      (node (ref "U3") (pin "41") (pinfunction "GPIO45_41") (pintype "passive"))
    )
    (net (code "54") (name "/GPIO46") (class "Default")
      (node (ref "J2") (pin "4") (pinfunction "4_4") (pintype "passive"))
      (node (ref "U3") (pin "44") (pinfunction "GPIO46_44") (pintype "passive"))
    )
    (net (code "55") (name "/GPIO47") (class "Default")
      (node (ref "J2") (pin "23") (pinfunction "23_23") (pintype "passive"))
      (node (ref "U3") (pin "27") (pinfunction "GPIO47/SPICLK_P_DIFF/SUBSPICLK_P_DIFF_27") (pintype "passive"))
    )
    (net (code "56") (name "/GPIO48") (class "Default")
      (node (ref "J2") (pin "22") (pinfunction "22_22") (pintype "passive"))
      (node (ref "U3") (pin "30") (pinfunction "GPIO48/SPICLK_N_DIFF/SUBSPICLK_N_DIFF_30") (pintype "passive"))
    )
    (net (code "57") (name "/RTS_FTDI") (class "Default")
      (node (ref "Q1") (pin "2") (pinfunction "E_2") (pintype "passive"))
      (node (ref "R17") (pin "1") (pinfunction "1_1") (pintype "passive"))
      (node (ref "U1") (pin "19") (pinfunction "~{RTS}_19") (pintype "passive"))
    )
    (net (code "58") (name "/RXD_FTDI") (class "Default")
      (node (ref "R18") (pin "2") (pinfunction "2_2") (pintype "passive"))
      (node (ref "U1") (pin "1") (pinfunction "RXD_1") (pintype "passive"))
    )
    (net (code "59") (name "/TXD_FTDI") (class "Default")
      (node (ref "R21") (pin "2") (pinfunction "2_2") (pintype "passive"))
      (node (ref "U1") (pin "17") (pinfunction "TXD_17") (pintype "passive"))
    )
    (net (code "60") (name "/U0RXD") (class "Default")
      (node (ref "J2") (pin "6") (pinfunction "6_6") (pintype "passive"))
      (node (ref "R21") (pin "1") (pinfunction "1_1") (pintype "passive"))
      (node (ref "U3") (pin "40") (pinfunction "U0RXD/GPIO44/CLK_OUT2_40") (pintype "passive"))
    )
    (net (code "61") (name "/U0TXD") (class "Default")
      (node (ref "J2") (pin "7") (pinfunction "7_7") (pintype "passive"))
      (node (ref "R18") (pin "1") (pinfunction "1_1") (pintype "passive"))
      (node (ref "U3") (pin "39") (pinfunction "U0TXD/GPIO43/CLK_OUT1_39") (pintype "passive"))
    )
    (net (code "62") (name "/VBUS_SENSE") (class "Default")
      (node (ref "R10") (pin "1") (pinfunction "1_1") (pintype "passive"))
      (node (ref "R13") (pin "2") (pinfunction "2_2") (pintype "passive"))
      (node (ref "U1") (pin "16") (pinfunction "CBUS3_16") (pintype "passive"))
    )
    (net (code "63") (name "GND") (class "Default")
      (node (ref "C1") (pin "1") (pinfunction "1_1") (pintype "passive"))
      (node (ref "C10") (pin "1") (pinfunction "1_1") (pintype "passive"))
      (node (ref "C11") (pin "1") (pinfunction "1_1") (pintype "passive"))
      (node (ref "C12") (pin "1") (pinfunction "1_1") (pintype "passive"))
      (node (ref "C13") (pin "1") (pinfunction "1_1") (pintype "passive"))
      (node (ref "C14") (pin "1") (pinfunction "1_1") (pintype "passive"))
      (node (ref "C15") (pin "1") (pinfunction "1_1") (pintype "passive"))
      (node (ref "C16") (pin "1") (pinfunction "1_1") (pintype "passive"))
      (node (ref "C17") (pin "1") (pinfunction "1_1") (pintype "passive"))
      (node (ref "C2") (pin "1") (pinfunction "1_1") (pintype "passive"))
      (node (ref "C3") (pin "1") (pinfunction "1_1") (pintype "passive"))
      (node (ref "C4") (pin "1") (pinfunction "1_1") (pintype "passive"))
      (node (ref "C5") (pin "1") (pinfunction "1_1") (pintype "passive"))
      (node (ref "C6") (pin "1") (pinfunction "1_1") (pintype "passive"))
      (node (ref "C7") (pin "1") (pinfunction "1_1") (pintype "passive"))
      (node (ref "C8") (pin "1") (pinfunction "1_1") (pintype "passive"))
      (node (ref "C9") (pin "1") (pinfunction "1_1") (pintype "passive"))
      (node (ref "D1") (pin "1") (pinfunction "1_1") (pintype "passive"))
      (node (ref "D3") (pin "1") (pinfunction "1_1") (pintype "passive"))
      (node (ref "D4") (pin "1") (pinfunction "1_1") (pintype "passive"))
      (node (ref "D5") (pin "1") (pinfunction "1_1") (pintype "passive"))
      (node (ref "D6") (pin "1") (pinfunction "1_1") (pintype "passive"))
      (node (ref "D7") (pin "1") (pinfunction "1_1") (pintype "passive"))
      (node (ref "D8") (pin "1") (pinfunction "1_1") (pintype "passive"))
      (node (ref "J1") (pin "1") (pinfunction "1_1") (pintype "passive"))
      (node (ref "J1") (pin "23") (pinfunction "23_23") (pintype "passive"))
      (node (ref "J2") (pin "2") (pinfunction "2_2") (pintype "passive"))
      (node (ref "J2") (pin "24") (pinfunction "24_24") (pintype "passive"))
      (node (ref "J3") (pin "A1B12") (pinfunction "GND_A1B12_A1B12") (pintype "passive"))
      (node (ref "J3") (pin "B1A12") (pinfunction "GND_B1A12_B1A12") (pintype "passive"))
      (node (ref "J3") (pin "S1") (pinfunction "SHIELD_1_S1") (pintype "passive"))
      (node (ref "J3") (pin "S2") (pinfunction "SHIELD_2_S2") (pintype "passive"))
      (node (ref "J3") (pin "S3") (pinfunction "SHIELD_3_S3") (pintype "passive"))
      (node (ref "J3") (pin "S4") (pinfunction "SHIELD_4_S4") (pintype "passive"))
      (node (ref "J4") (pin "A1B12") (pinfunction "GND_A1B12_A1B12") (pintype "passive"))
      (node (ref "J4") (pin "B1A12") (pinfunction "GND_B1A12_B1A12") (pintype "passive"))
      (node (ref "J4") (pin "S1") (pinfunction "SHIELD_1_S1") (pintype "passive"))
      (node (ref "J4") (pin "S2") (pinfunction "SHIELD_2_S2") (pintype "passive"))
      (node (ref "J4") (pin "S3") (pinfunction "SHIELD_3_S3") (pintype "passive"))
      (node (ref "J4") (pin "S4") (pinfunction "SHIELD_4_S4") (pintype "passive"))
      (node (ref "R11") (pin "1") (pinfunction "1_1") (pintype "passive"))
      (node (ref "R12") (pin "1") (pinfunction "1_1") (pintype "passive"))
      (node (ref "R13") (pin "1") (pinfunction "1_1") (pintype "passive"))
      (node (ref "R14") (pin "1") (pinfunction "1_1") (pintype "passive"))
      (node (ref "R15") (pin "1") (pinfunction "1_1") (pintype "passive"))
      (node (ref "R9") (pin "2") (pinfunction "2_2") (pintype "passive"))
      (node (ref "SW1") (pin "3") (pinfunction "3_3") (pintype "passive"))
      (node (ref "SW1") (pin "4") (pinfunction "4_4") (pintype "passive"))
      (node (ref "SW2") (pin "3") (pinfunction "3_3") (pintype "passive"))
      (node (ref "SW2") (pin "4") (pinfunction "4_4") (pintype "passive"))
      (node (ref "U1") (pin "13") (pinfunction "GND_13") (pintype "passive"))
      (node (ref "U1") (pin "21") (pinfunction "GND_21") (pintype "passive"))
      (node (ref "U1") (pin "3") (pinfunction "GND_3") (pintype "passive"))
      (node (ref "U2") (pin "2") (pinfunction "GND_2") (pintype "power_in"))
      (node (ref "U2") (pin "4") (pinfunction "GND_4") (pintype "power_in"))
      (node (ref "U3") (pin "1") (pinfunction "GND_01_1") (pintype "passive"))
      (node (ref "U3") (pin "2") (pinfunction "GND_02_2") (pintype "passive"))
      (node (ref "U3") (pin "42") (pinfunction "GND_42") (pintype "passive"))
      (node (ref "U3") (pin "43") (pinfunction "GND_43") (pintype "passive"))
      (node (ref "U3") (pin "46") (pinfunction "GND_46_46") (pintype "passive"))
      (node (ref "U3") (pin "47") (pinfunction "GND_47_47") (pintype "passive"))
      (node (ref "U3") (pin "48") (pinfunction "GND_48_48") (pintype "passive"))
      (node (ref "U3") (pin "49") (pinfunction "GND_49_49") (pintype "passive"))
      (node (ref "U3") (pin "50") (pinfunction "GND_50_50") (pintype "passive"))
      (node (ref "U3") (pin "51") (pinfunction "GND_51_51") (pintype "passive"))
      (node (ref "U3") (pin "52") (pinfunction "GND_52_52") (pintype "passive"))
      (node (ref "U3") (pin "53") (pinfunction "GND_53_53") (pintype "passive"))
      (node (ref "U3") (pin "54") (pinfunction "GND_54_54") (pintype "passive"))
      (node (ref "U3") (pin "55") (pinfunction "GND_55_55") (pintype "passive"))
      (node (ref "U3") (pin "56") (pinfunction "GND_56_56") (pintype "passive"))
      (node (ref "U3") (pin "57") (pinfunction "GND_57_57") (pintype "passive"))
      (node (ref "U3") (pin "58") (pinfunction "GND_58_58") (pintype "passive"))
      (node (ref "U3") (pin "59") (pinfunction "GND_59_59") (pintype "passive"))
      (node (ref "U3") (pin "60") (pinfunction "GND_60_60") (pintype "passive"))
      (node (ref "U3") (pin "61") (pinfunction "GND_61_61") (pintype "passive"))
      (node (ref "U3") (pin "62") (pinfunction "GND_62_62") (pintype "passive"))
      (node (ref "U3") (pin "63") (pinfunction "GND_63_63") (pintype "passive"))
      (node (ref "U3") (pin "64") (pinfunction "GND_64_64") (pintype "passive"))
      (node (ref "U3") (pin "65") (pinfunction "GND_65_65") (pintype "passive"))
      (node (ref "U3") (pin "66") (pinfunction "GND_66_66") (pintype "passive"))
      (node (ref "U3") (pin "67") (pinfunction "GND_67_67") (pintype "passive"))
      (node (ref "U3") (pin "68") (pinfunction "GND_68_68") (pintype "passive"))
      (node (ref "U3") (pin "69") (pinfunction "GND_69_69") (pintype "passive"))
      (node (ref "U3") (pin "70") (pinfunction "GND_70_70") (pintype "passive"))
      (node (ref "U3") (pin "71") (pinfunction "GND_71_71") (pintype "passive"))
      (node (ref "U3") (pin "72") (pinfunction "GND_72_72") (pintype "passive"))
      (node (ref "U3") (pin "73") (pinfunction "GND_73_73") (pintype "passive"))
    )
    (net (code "64") (name "Net-(D1-Pad2)") (class "Default")
      (node (ref "D1") (pin "2") (pinfunction "2_2") (pintype "passive"))
      (node (ref "R4") (pin "1") (pinfunction "1_1") (pintype "passive"))
    )
    (net (code "65") (name "Net-(D2-Pad2)") (class "Default")
      (node (ref "D2") (pin "2") (pinfunction "2_2") (pintype "passive"))
      (node (ref "R5") (pin "1") (pinfunction "1_1") (pintype "passive"))
    )
    (net (code "66") (name "Net-(J3-CC1)") (class "Default")
      (node (ref "J3") (pin "A5") (pinfunction "CC1_A5") (pintype "passive"))
      (node (ref "R12") (pin "2") (pinfunction "2_2") (pintype "passive"))
    )
    (net (code "67") (name "Net-(J3-CC2)") (class "Default")
      (node (ref "J3") (pin "B5") (pinfunction "CC2_B5") (pintype "passive"))
      (node (ref "R11") (pin "2") (pinfunction "2_2") (pintype "passive"))
    )
    (net (code "68") (name "Net-(J4-CC1)") (class "Default")
      (node (ref "J4") (pin "A5") (pinfunction "CC1_A5") (pintype "passive"))
      (node (ref "R15") (pin "2") (pinfunction "2_2") (pintype "passive"))
    )
    (net (code "69") (name "Net-(J4-CC2)") (class "Default")
      (node (ref "J4") (pin "B5") (pinfunction "CC2_B5") (pintype "passive"))
      (node (ref "R14") (pin "2") (pinfunction "2_2") (pintype "passive"))
    )
    (net (code "70") (name "Net-(Q1-B)") (class "Default")
      (node (ref "Q1") (pin "1") (pinfunction "B_1") (pintype "passive"))
      (node (ref "R16") (pin "2") (pinfunction "2_2") (pintype "passive"))
    )
    (net (code "71") (name "Net-(Q2-B)") (class "Default")
      (node (ref "Q2") (pin "1") (pinfunction "B_1") (pintype "passive"))
      (node (ref "R17") (pin "2") (pinfunction "2_2") (pintype "passive"))
    )
    (net (code "72") (name "Net-(U1-CBUS0)") (class "Default")
      (node (ref "R9") (pin "1") (pinfunction "1_1") (pintype "passive"))
      (node (ref "U1") (pin "15") (pinfunction "CBUS0_15") (pintype "passive"))
    )
    (net (code "73") (name "Net-(U1-~{RESET})") (class "Default")
      (node (ref "C5") (pin "2") (pinfunction "2_2") (pintype "passive"))
      (node (ref "R8") (pin "2") (pinfunction "2_2") (pintype "passive"))
      (node (ref "U1") (pin "11") (pinfunction "~{RESET}_11") (pintype "passive"))
    )
    (net (code "74") (name "unconnected-(J1-Pad24)") (class "Default")
      (node (ref "J1") (pin "24") (pinfunction "24_24") (pintype "passive+no_connect"))
    )
    (net (code "75") (name "unconnected-(J3-SBU1-PadA8)") (class "Default")
      (node (ref "J3") (pin "A8") (pinfunction "SBU1_A8") (pintype "passive+no_connect"))
    )
    (net (code "76") (name "unconnected-(J3-SBU2-PadB8)") (class "Default")
      (node (ref "J3") (pin "B8") (pinfunction "SBU2_B8") (pintype "passive+no_connect"))
    )
    (net (code "77") (name "unconnected-(J4-SBU1-PadA8)") (class "Default")
      (node (ref "J4") (pin "A8") (pinfunction "SBU1_A8") (pintype "passive+no_connect"))
    )
    (net (code "78") (name "unconnected-(J4-SBU2-PadB8)") (class "Default")
      (node (ref "J4") (pin "B8") (pinfunction "SBU2_B8") (pintype "passive+no_connect"))
    )
    (net (code "79") (name "unconnected-(U1-CBUS1-Pad14)") (class "Default")
      (node (ref "U1") (pin "14") (pinfunction "CBUS1_14") (pintype "passive+no_connect"))
    )
    (net (code "80") (name "unconnected-(U1-CBUS2-Pad7)") (class "Default")
      (node (ref "U1") (pin "7") (pinfunction "CBUS2_7") (pintype "passive+no_connect"))
    )
    (net (code "81") (name "unconnected-(U1-~{CTS}-Pad6)") (class "Default")
      (node (ref "U1") (pin "6") (pinfunction "~{CTS}_6") (pintype "passive+no_connect"))
    )
    (net (code "82") (name "unconnected-(U1-~{DCD}-Pad5)") (class "Default")
      (node (ref "U1") (pin "5") (pinfunction "~{DCD}_5") (pintype "passive+no_connect"))
    )
    (net (code "83") (name "unconnected-(U1-~{DSR}-Pad4)") (class "Default")
      (node (ref "U1") (pin "4") (pinfunction "~{DSR}_4") (pintype "passive+no_connect"))
    )
    (net (code "84") (name "unconnected-(U1-~{RI}-Pad2)") (class "Default")
      (node (ref "U1") (pin "2") (pinfunction "~{RI}_2") (pintype "passive+no_connect"))
    )
  )
)
